# DM2080_VGA_ToF.net
KiCad netlist of a schematic drawn in Altium Designer
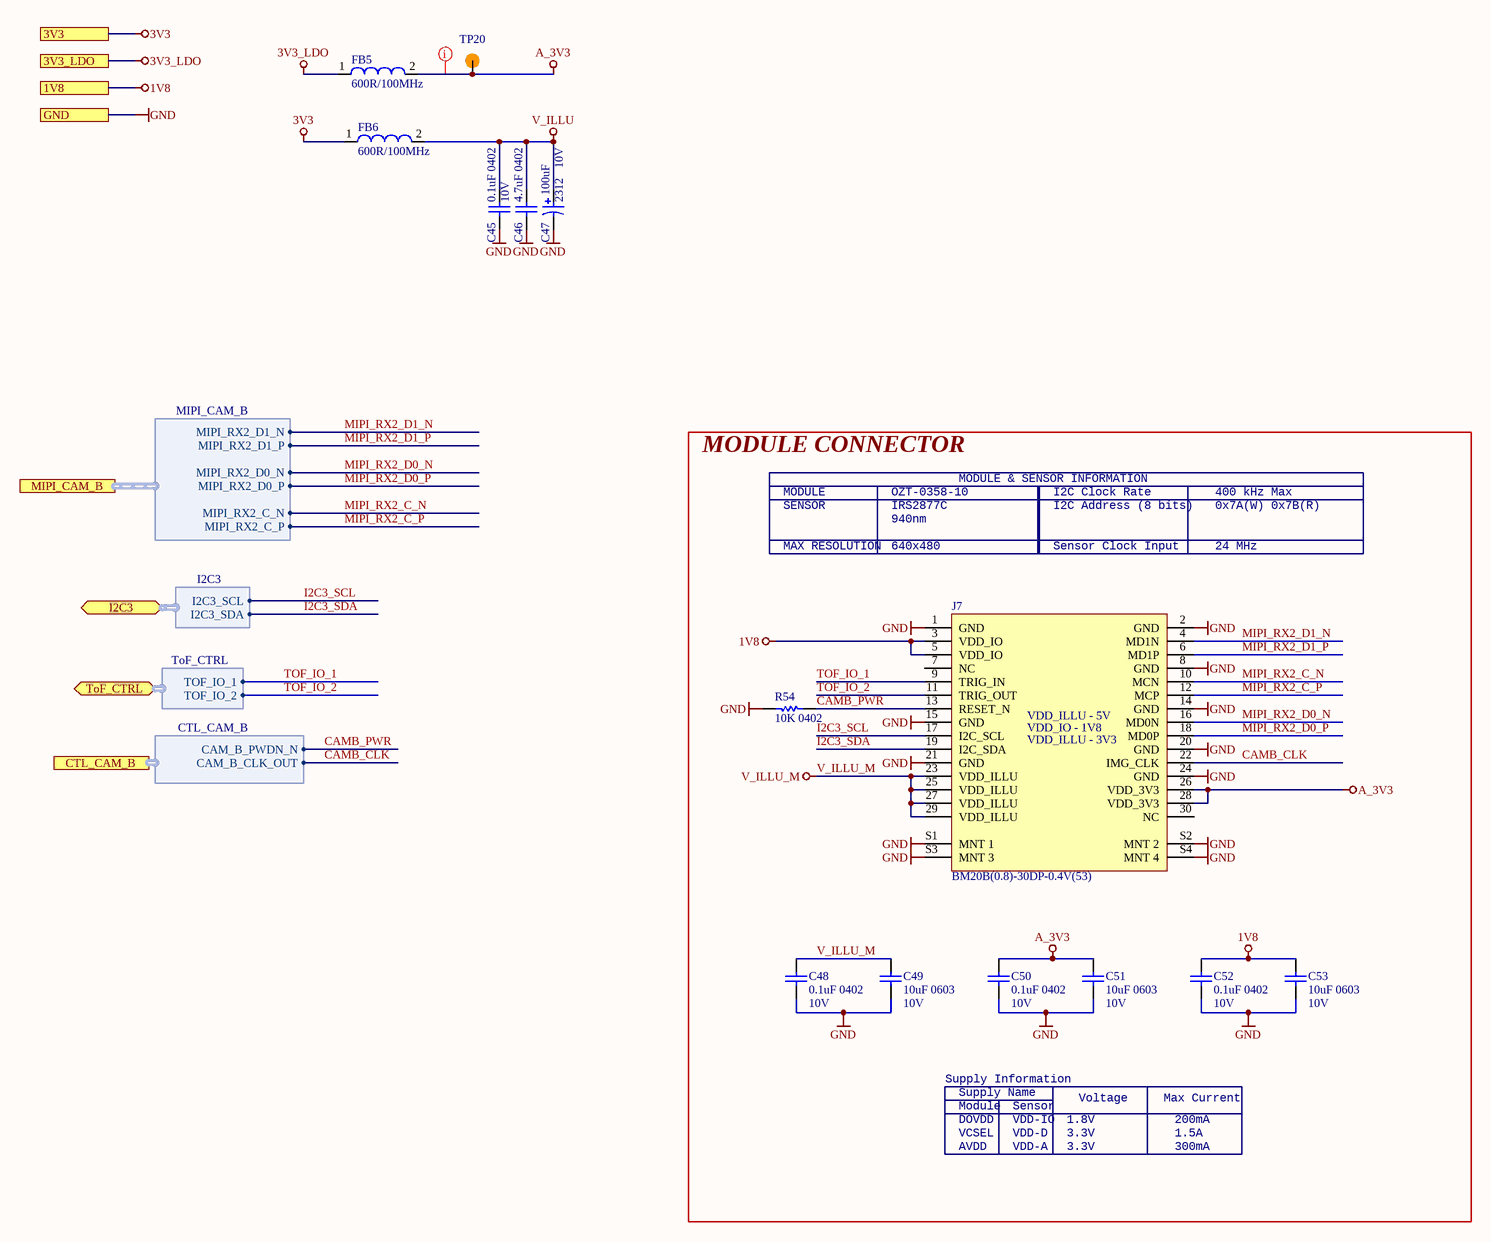
[diagram p0: DM2080_VGA_ToF.SchDoc]

(export (version "E")
  (design (tool "Eeschema 10.0.6"))
  (components
    (comp (ref "C45")
      (value "0.1uF 0402")
      (footprint "CAP_Altium_Vault_Generic:CAPC0402(1005)70_L")
      (description "CAP CER 0.1UF 10V X7R 0402 5%")
      (fields (field (name "TOLERANCE") "5%") (field (name "VOLTAGE RATING") "10V"))
      (libsource (lib "LuxonisMaster") (part "GRM155R71A104JA01D"))
    )
    (comp (ref "C46")
      (value "4.7uF 0402")
      (footprint "CAP_Altium_Vault_Generic:CAPC0402(1005)70_L")
      (description "CAP CER 4.7UF 6.3V X5R 0402")
      (fields (field (name "TOLERANCE") "20%") (field (name "VOLTAGE") "6.3V"))
      (libsource (lib "LuxonisMaster") (part "GRM155R60J475ME87D"))
    )
    (comp (ref "C47")
      (value "TAJC107K010RNJ")
      (footprint "AVX-TAJ-C-2_L")
      (fields
        (field (name "SIZE CODE") "2312")
        (field (name "RATED DC VOLTAGE (URDC)") "10V")
        (field (name "CAPACITANCE") "100uF")
      )
      (libsource (lib "NG3398C-RA") (part "TAJC107K010RNJ"))
    )
    (comp (ref "C48")
      (value "0.1uF 0402")
      (footprint "CAP_Altium_Vault_Generic:CAPC0402(1005)70_L")
      (description "CAP CER 0.1UF 10V X7R 0402 5%")
      (fields (field (name "TOLERANCE") "5%") (field (name "VOLTAGE RATING") "10V"))
      (libsource (lib "LuxonisMaster") (part "GRM155R71A104JA01D"))
    )
    (comp (ref "C49")
      (value "10uF 0603")
      (footprint "CAP_Altium_Vault_Generic:CAPC0603(1608)100_L")
      (description "CAP CER 10UF 10V X5R 0603 20%")
      (fields (field (name "TOLERANCE") "20%") (field (name "VOLTAGE RATING") "10V"))
      (libsource (lib "LuxonisMaster") (part "GRM188R61A106ME69D"))
    )
    (comp (ref "C50")
      (value "0.1uF 0402")
      (footprint "CAP_Altium_Vault_Generic:CAPC0402(1005)70_L")
      (description "CAP CER 0.1UF 10V X7R 0402 5%")
      (fields (field (name "TOLERANCE") "5%") (field (name "VOLTAGE RATING") "10V"))
      (libsource (lib "LuxonisMaster") (part "GRM155R71A104JA01D"))
    )
    (comp (ref "C51")
      (value "10uF 0603")
      (footprint "CAP_Altium_Vault_Generic:CAPC0603(1608)100_L")
      (description "CAP CER 10UF 10V X5R 0603 20%")
      (fields (field (name "TOLERANCE") "20%") (field (name "VOLTAGE RATING") "10V"))
      (libsource (lib "LuxonisMaster") (part "GRM188R61A106ME69D"))
    )
    (comp (ref "C52")
      (value "0.1uF 0402")
      (footprint "CAP_Altium_Vault_Generic:CAPC0402(1005)70_L")
      (description "CAP CER 0.1UF 10V X7R 0402 5%")
      (fields (field (name "TOLERANCE") "5%") (field (name "VOLTAGE RATING") "10V"))
      (libsource (lib "LuxonisMaster") (part "GRM155R71A104JA01D"))
    )
    (comp (ref "C53")
      (value "10uF 0603")
      (footprint "CAP_Altium_Vault_Generic:CAPC0603(1608)100_L")
      (description "CAP CER 10UF 10V X5R 0603 20%")
      (fields (field (name "TOLERANCE") "20%") (field (name "VOLTAGE RATING") "10V"))
      (libsource (lib "LuxonisMaster") (part "GRM188R61A106ME69D"))
    )
    (comp (ref "FB5")
      (value "600R/100MHz")
      (footprint "LuxonisMaster:2508056017Y2")
      (description "FERRITE BEAD, 0.1OHM, 2A, 0805, 600R/100MHz")
      (fields (field (name "TOLERANCE") "25%"))
      (libsource (lib "LuxonisMaster") (part "2508056017Y2"))
    )
    (comp (ref "FB6")
      (value "600R/100MHz")
      (footprint "LuxonisMaster:2508056017Y2")
      (description "FERRITE BEAD, 0.1OHM, 2A, 0805, 600R/100MHz")
      (fields (field (name "TOLERANCE") "25%"))
      (libsource (lib "LuxonisMaster") (part "2508056017Y2"))
    )
    (comp (ref "J7")
      (value "BM20B(0.8)-30DP-0.4V(53)")
      (footprint "VGA-TOF-OZT-0358-10")
      (libsource (lib "NG3398C-RA") (part "VGA-TOF-OZT-0358-10"))
    )
    (comp (ref "R54")
      (value "10K 0402")
      (footprint "RES_Altium_Vault_Generic:RESC0402(1005)_L")
      (description "RES SMD 10K OHM 1% 1/16W 0402")
      (fields (field (name "TOLERANCE") "1%"))
      (libsource (lib "LuxonisMaster") (part "RC0402FR-1310KL"))
    )
    (comp (ref "TP20")
      (value "TP100_150_NS")
      (footprint "LuxonisMaster:TP100_150_NS")
      (libsource (lib "LuxonisMaster") (part "TEST_POINT"))
    )
  )
  (nets
    (net (code "5") (name "/CAMB_CLK") (class "Default")
      (node (ref "J7") (pin "22") (pinfunction "IMG_CLK_22") (pintype "passive"))
    )
    (net (code "6") (name "/CAMB_PWR") (class "Default")
      (node (ref "J7") (pin "13") (pinfunction "RESET_N_13") (pintype "passive"))
      (node (ref "R54") (pin "2") (pinfunction "2_2") (pintype "passive"))
    )
    (net (code "7") (name "/I2C3_SCL") (class "Default")
      (node (ref "J7") (pin "17") (pinfunction "I2C_SCL_17") (pintype "passive"))
    )
    (net (code "8") (name "/I2C3_SDA") (class "Default")
      (node (ref "J7") (pin "19") (pinfunction "I2C_SDA_19") (pintype "passive"))
    )
    (net (code "9") (name "/MIPI_RX2_C_N") (class "Default")
      (node (ref "J7") (pin "10") (pinfunction "MCN_10") (pintype "passive"))
    )
    (net (code "10") (name "/MIPI_RX2_C_P") (class "Default")
      (node (ref "J7") (pin "12") (pinfunction "MCP_12") (pintype "passive"))
    )
    (net (code "11") (name "/MIPI_RX2_D0_N") (class "Default")
      (node (ref "J7") (pin "16") (pinfunction "MD0N_16") (pintype "passive"))
    )
    (net (code "12") (name "/MIPI_RX2_D0_P") (class "Default")
      (node (ref "J7") (pin "18") (pinfunction "MD0P_18") (pintype "passive"))
    )
    (net (code "13") (name "/MIPI_RX2_D1_N") (class "Default")
      (node (ref "J7") (pin "4") (pinfunction "MD1N_4") (pintype "passive"))
    )
    (net (code "14") (name "/MIPI_RX2_D1_P") (class "Default")
      (node (ref "J7") (pin "6") (pinfunction "MD1P_6") (pintype "passive"))
    )
    (net (code "15") (name "/TOF_IO_1") (class "Default")
      (node (ref "J7") (pin "9") (pinfunction "TRIG_IN_9") (pintype "passive"))
    )
    (net (code "16") (name "/TOF_IO_2") (class "Default")
      (node (ref "J7") (pin "11") (pinfunction "TRIG_OUT_11") (pintype "passive"))
    )
    (net (code "21") (name "1V8") (class "Default")
      (node (ref "C52") (pin "2") (pinfunction "2_2") (pintype "passive"))
      (node (ref "C53") (pin "2") (pinfunction "2_2") (pintype "passive"))
      (node (ref "J7") (pin "3") (pinfunction "VDD_IO_3") (pintype "passive"))
      (node (ref "J7") (pin "5") (pinfunction "VDD_IO_5") (pintype "passive"))
    )
    (net (code "22") (name "3V3") (class "Default")
      (node (ref "FB6") (pin "1") (pinfunction "1_1") (pintype "passive"))
    )
    (net (code "23") (name "3V3_LDO") (class "Default")
      (node (ref "FB5") (pin "1") (pinfunction "1_1") (pintype "passive"))
    )
    (net (code "24") (name "A_3V3") (class "Default")
      (node (ref "C50") (pin "2") (pinfunction "2_2") (pintype "passive"))
      (node (ref "C51") (pin "2") (pinfunction "2_2") (pintype "passive"))
      (node (ref "FB5") (pin "2") (pinfunction "2_2") (pintype "passive"))
      (node (ref "J7") (pin "26") (pinfunction "VDD_3V3_26") (pintype "passive"))
      (node (ref "J7") (pin "28") (pinfunction "VDD_3V3_28") (pintype "passive"))
      (node (ref "TP20") (pin "1") (pintype "passive"))
    )
    (net (code "25") (name "GND") (class "Default")
      (node (ref "C45") (pin "1") (pinfunction "1_1") (pintype "passive"))
      (node (ref "C46") (pin "1") (pinfunction "1_1") (pintype "passive"))
      (node (ref "C47") (pin "2") (pinfunction "2_2") (pintype "passive"))
      (node (ref "C48") (pin "1") (pinfunction "1_1") (pintype "passive"))
      (node (ref "C49") (pin "1") (pinfunction "1_1") (pintype "passive"))
      (node (ref "C50") (pin "1") (pinfunction "1_1") (pintype "passive"))
      (node (ref "C51") (pin "1") (pinfunction "1_1") (pintype "passive"))
      (node (ref "C52") (pin "1") (pinfunction "1_1") (pintype "passive"))
      (node (ref "C53") (pin "1") (pinfunction "1_1") (pintype "passive"))
      (node (ref "J7") (pin "1") (pinfunction "GND_1") (pintype "passive"))
      (node (ref "J7") (pin "14") (pinfunction "GND_14") (pintype "passive"))
      (node (ref "J7") (pin "15") (pinfunction "GND_15") (pintype "passive"))
      (node (ref "J7") (pin "2") (pinfunction "GND_2") (pintype "passive"))
      (node (ref "J7") (pin "20") (pinfunction "GND_20") (pintype "passive"))
      (node (ref "J7") (pin "21") (pinfunction "GND_21") (pintype "passive"))
      (node (ref "J7") (pin "24") (pinfunction "GND_24") (pintype "passive"))
      (node (ref "J7") (pin "8") (pinfunction "GND_8") (pintype "passive"))
      (node (ref "J7") (pin "S1") (pinfunction "MNT_1_S1") (pintype "passive"))
      (node (ref "J7") (pin "S2") (pinfunction "MNT_2_S2") (pintype "passive"))
      (node (ref "J7") (pin "S3") (pinfunction "MNT_3_S3") (pintype "passive"))
      (node (ref "J7") (pin "S4") (pinfunction "MNT_4_S4") (pintype "passive"))
      (node (ref "R54") (pin "1") (pinfunction "1_1") (pintype "passive"))
    )
    (net (code "26") (name "V_ILLU") (class "Default")
      (node (ref "C45") (pin "2") (pinfunction "2_2") (pintype "passive"))
      (node (ref "C46") (pin "2") (pinfunction "2_2") (pintype "passive"))
      (node (ref "C47") (pin "1") (pinfunction "1_1") (pintype "passive"))
      (node (ref "FB6") (pin "2") (pinfunction "2_2") (pintype "passive"))
    )
    (net (code "27") (name "V_ILLU_M") (class "Default")
      (node (ref "C48") (pin "2") (pinfunction "2_2") (pintype "passive"))
      (node (ref "C49") (pin "2") (pinfunction "2_2") (pintype "passive"))
      (node (ref "J7") (pin "23") (pinfunction "VDD_ILLU_23") (pintype "passive"))
      (node (ref "J7") (pin "25") (pinfunction "VDD_ILLU_25") (pintype "passive"))
      (node (ref "J7") (pin "27") (pinfunction "VDD_ILLU_27") (pintype "passive"))
      (node (ref "J7") (pin "29") (pinfunction "VDD_ILLU_29") (pintype "passive"))
    )
    (net (code "28") (name "unconnected-(J7-NC-Pad7)") (class "Default")
      (node (ref "J7") (pin "7") (pinfunction "NC_7") (pintype "passive"))
    )
    (net (code "29") (name "unconnected-(J7-NC-Pad30)") (class "Default")
      (node (ref "J7") (pin "30") (pinfunction "NC_30") (pintype "passive"))
    )
  )
)
